# capelet_nrf52.net
KiCad netlist of a schematic drawn in EAGLE
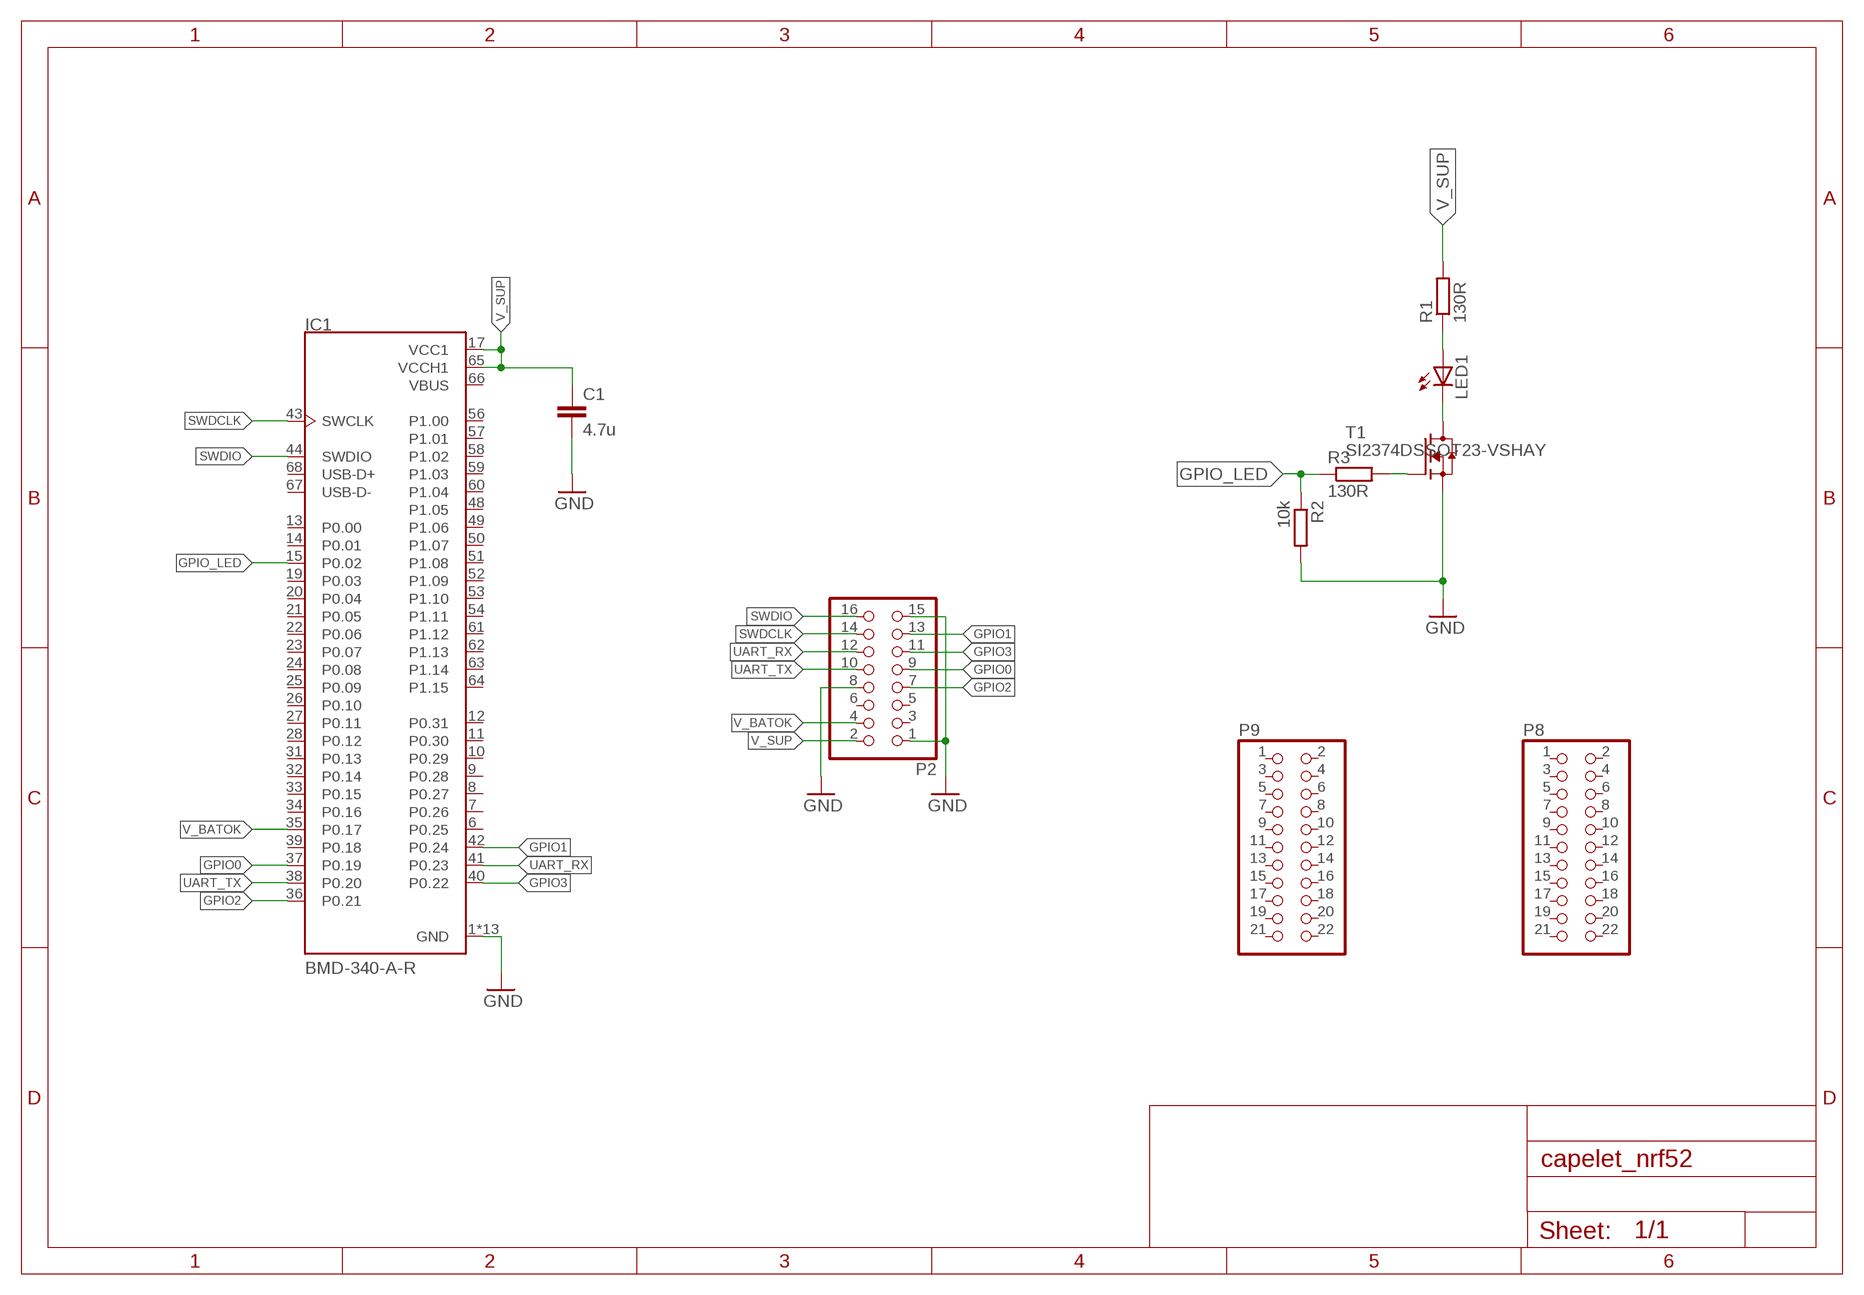
[diagram p0: schematic, sheet 1]

(export (version "E")
  (design (tool "Eeschema 10.0.6"))
  (components
    (comp (ref "C1")
      (value "4.7u")
      (footprint "eagle-import:CAPC1608X95")
      (libsource (lib "eagle-import") (part "C_SMD0603"))
    )
    (comp (ref "IC1")
      (value "BMD-340-A-R")
      (footprint "eagle-import:RIGADO_BMD-340-A-R")
      (fields (field (name "MF") "Rigado"))
      (libsource (lib "eagle-import") (part "BMD-340-A-R"))
    )
    (comp (ref "LED1")
      (value "598-8130-107FLED_0805")
      (footprint "eagle-import:LEDC2012X75")
      (libsource (lib "eagle-import") (part "598-8130-107FLED_0805"))
    )
    (comp (ref "P2")
      (value "PINHD-2X8")
      (footprint "eagle-import:2X08")
      (libsource (lib "eagle-import") (part "PINHD-2X8"))
    )
    (comp (ref "P8")
      (value "PINHD-2X11")
      (footprint "eagle-import:2X11")
      (libsource (lib "eagle-import") (part "PINHD-2X11"))
    )
    (comp (ref "P9")
      (value "PINHD-2X11")
      (footprint "eagle-import:2X11")
      (libsource (lib "eagle-import") (part "PINHD-2X11"))
    )
    (comp (ref "R1")
      (value "130R")
      (footprint "eagle-import:RESC2012X65")
      (libsource (lib "eagle-import") (part "R_SMD0805"))
    )
    (comp (ref "R2")
      (value "10k")
      (footprint "eagle-import:RESC2012X65")
      (libsource (lib "eagle-import") (part "R_SMD0805"))
    )
    (comp (ref "R3")
      (value "130R")
      (footprint "eagle-import:RESC2012X65")
      (libsource (lib "eagle-import") (part "R_SMD0805"))
    )
    (comp (ref "T1")
      (value "SI2374DSSOT23-VSHAY")
      (footprint "eagle-import:SOT95P237X112-3")
      (libsource (lib "eagle-import") (part "SI2374DSSOT23-VSHAY"))
    )
  )
  (nets
    (net (code "1") (name "/VBUS") (class "Default")
      (node (ref "IC1") (pin "66") (pinfunction "VBUS_66") (pintype "power_in"))
    )
    (net (code "2") (name "GND") (class "Default")
      (node (ref "C1") (pin "2") (pinfunction "2_2") (pintype "passive"))
      (node (ref "IC1") (pin "1") (pinfunction "GND_1") (pintype "power_in"))
      (node (ref "IC1") (pin "16") (pinfunction "GND_16") (pintype "power_in"))
      (node (ref "IC1") (pin "18") (pinfunction "GND_18") (pintype "power_in"))
      (node (ref "IC1") (pin "2") (pinfunction "GND_2") (pintype "power_in"))
      (node (ref "IC1") (pin "29") (pinfunction "GND_29") (pintype "power_in"))
      (node (ref "IC1") (pin "3") (pinfunction "GND_3") (pintype "power_in"))
      (node (ref "IC1") (pin "30") (pinfunction "GND_30") (pintype "power_in"))
      (node (ref "IC1") (pin "4") (pinfunction "GND_4") (pintype "power_in"))
      (node (ref "IC1") (pin "45") (pinfunction "GND_45") (pintype "power_in"))
      (node (ref "IC1") (pin "46") (pinfunction "GND_46") (pintype "power_in"))
      (node (ref "IC1") (pin "47") (pinfunction "GND_47") (pintype "power_in"))
      (node (ref "IC1") (pin "5") (pinfunction "GND_5") (pintype "power_in"))
      (node (ref "IC1") (pin "55") (pinfunction "GND_55") (pintype "power_in"))
      (node (ref "P2") (pin "1") (pinfunction "1_1") (pintype "passive"))
      (node (ref "P2") (pin "15") (pinfunction "15_15") (pintype "passive"))
      (node (ref "P2") (pin "8") (pinfunction "8_8") (pintype "passive"))
      (node (ref "R2") (pin "2") (pinfunction "2_2") (pintype "passive"))
      (node (ref "T1") (pin "2") (pinfunction "S_2") (pintype "passive"))
    )
    (net (code "3") (name "GPIO0") (class "Default")
      (node (ref "IC1") (pin "37") (pinfunction "P0.19_37") (pintype "bidirectional"))
      (node (ref "P2") (pin "9") (pinfunction "9_9") (pintype "passive"))
    )
    (net (code "4") (name "GPIO1") (class "Default")
      (node (ref "IC1") (pin "42") (pinfunction "P0.24_42") (pintype "bidirectional"))
      (node (ref "P2") (pin "13") (pinfunction "13_13") (pintype "passive"))
    )
    (net (code "5") (name "GPIO2") (class "Default")
      (node (ref "IC1") (pin "36") (pinfunction "P0.21_36") (pintype "bidirectional"))
      (node (ref "P2") (pin "7") (pinfunction "7_7") (pintype "passive"))
    )
    (net (code "6") (name "GPIO3") (class "Default")
      (node (ref "IC1") (pin "40") (pinfunction "P0.22_40") (pintype "bidirectional"))
      (node (ref "P2") (pin "11") (pinfunction "11_11") (pintype "passive"))
    )
    (net (code "7") (name "GPIO_LED") (class "Default")
      (node (ref "IC1") (pin "15") (pinfunction "P0.02_15") (pintype "bidirectional"))
      (node (ref "R2") (pin "1") (pinfunction "1_1") (pintype "passive"))
      (node (ref "R3") (pin "1") (pinfunction "1_1") (pintype "passive"))
    )
    (net (code "8") (name "Net-(LED1-A)") (class "Default")
      (node (ref "LED1") (pin "2") (pinfunction "A_2") (pintype "passive"))
      (node (ref "R1") (pin "1") (pinfunction "1_1") (pintype "passive"))
    )
    (net (code "9") (name "Net-(LED1-C)") (class "Default")
      (node (ref "LED1") (pin "1") (pinfunction "C_1") (pintype "passive"))
      (node (ref "T1") (pin "3") (pinfunction "D_3") (pintype "passive"))
    )
    (net (code "10") (name "Net-(T1-G)") (class "Default")
      (node (ref "R3") (pin "2") (pinfunction "2_2") (pintype "passive"))
      (node (ref "T1") (pin "1") (pinfunction "G_1") (pintype "passive"))
    )
    (net (code "11") (name "SWDCLK") (class "Default")
      (node (ref "IC1") (pin "43") (pinfunction "SWCLK_43") (pintype "input"))
      (node (ref "P2") (pin "14") (pinfunction "14_14") (pintype "passive"))
    )
    (net (code "12") (name "SWDIO") (class "Default")
      (node (ref "IC1") (pin "44") (pinfunction "SWDIO_44") (pintype "bidirectional"))
      (node (ref "P2") (pin "16") (pinfunction "16_16") (pintype "passive"))
    )
    (net (code "13") (name "UART_RX") (class "Default")
      (node (ref "IC1") (pin "41") (pinfunction "P0.23_41") (pintype "bidirectional"))
      (node (ref "P2") (pin "12") (pinfunction "12_12") (pintype "passive"))
    )
    (net (code "14") (name "UART_TX") (class "Default")
      (node (ref "IC1") (pin "38") (pinfunction "P0.20_38") (pintype "bidirectional"))
      (node (ref "P2") (pin "10") (pinfunction "10_10") (pintype "passive"))
    )
    (net (code "15") (name "V_BATOK") (class "Default")
      (node (ref "IC1") (pin "35") (pinfunction "P0.17_35") (pintype "bidirectional"))
      (node (ref "P2") (pin "4") (pinfunction "4_4") (pintype "passive"))
    )
    (net (code "16") (name "V_SUP") (class "Default")
      (node (ref "C1") (pin "1") (pinfunction "1_1") (pintype "passive"))
      (node (ref "IC1") (pin "17") (pinfunction "VCC1_17") (pintype "power_in"))
      (node (ref "IC1") (pin "65") (pinfunction "VCCH1_65") (pintype "power_in"))
      (node (ref "P2") (pin "2") (pinfunction "2_2") (pintype "passive"))
      (node (ref "R1") (pin "2") (pinfunction "2_2") (pintype "passive"))
    )
    (net (code "17") (name "unconnected-(IC1-P0.00-Pad13)") (class "Default")
      (node (ref "IC1") (pin "13") (pinfunction "P0.00_13") (pintype "bidirectional"))
    )
    (net (code "18") (name "unconnected-(IC1-P0.01-Pad14)") (class "Default")
      (node (ref "IC1") (pin "14") (pinfunction "P0.01_14") (pintype "bidirectional"))
    )
    (net (code "19") (name "unconnected-(IC1-P0.03-Pad19)") (class "Default")
      (node (ref "IC1") (pin "19") (pinfunction "P0.03_19") (pintype "bidirectional"))
    )
    (net (code "20") (name "unconnected-(IC1-P0.04-Pad20)") (class "Default")
      (node (ref "IC1") (pin "20") (pinfunction "P0.04_20") (pintype "bidirectional"))
    )
    (net (code "21") (name "unconnected-(IC1-P0.05-Pad21)") (class "Default")
      (node (ref "IC1") (pin "21") (pinfunction "P0.05_21") (pintype "bidirectional"))
    )
    (net (code "22") (name "unconnected-(IC1-P0.06-Pad22)") (class "Default")
      (node (ref "IC1") (pin "22") (pinfunction "P0.06_22") (pintype "bidirectional"))
    )
    (net (code "23") (name "unconnected-(IC1-P0.07-Pad23)") (class "Default")
      (node (ref "IC1") (pin "23") (pinfunction "P0.07_23") (pintype "bidirectional"))
    )
    (net (code "24") (name "unconnected-(IC1-P0.08-Pad24)") (class "Default")
      (node (ref "IC1") (pin "24") (pinfunction "P0.08_24") (pintype "bidirectional"))
    )
    (net (code "25") (name "unconnected-(IC1-P0.09-Pad25)") (class "Default")
      (node (ref "IC1") (pin "25") (pinfunction "P0.09_25") (pintype "bidirectional"))
    )
    (net (code "26") (name "unconnected-(IC1-P0.10-Pad26)") (class "Default")
      (node (ref "IC1") (pin "26") (pinfunction "P0.10_26") (pintype "bidirectional"))
    )
    (net (code "27") (name "unconnected-(IC1-P0.11-Pad27)") (class "Default")
      (node (ref "IC1") (pin "27") (pinfunction "P0.11_27") (pintype "bidirectional"))
    )
    (net (code "28") (name "unconnected-(IC1-P0.12-Pad28)") (class "Default")
      (node (ref "IC1") (pin "28") (pinfunction "P0.12_28") (pintype "bidirectional"))
    )
    (net (code "29") (name "unconnected-(IC1-P0.13-Pad31)") (class "Default")
      (node (ref "IC1") (pin "31") (pinfunction "P0.13_31") (pintype "bidirectional"))
    )
    (net (code "30") (name "unconnected-(IC1-P0.14-Pad32)") (class "Default")
      (node (ref "IC1") (pin "32") (pinfunction "P0.14_32") (pintype "bidirectional"))
    )
    (net (code "31") (name "unconnected-(IC1-P0.15-Pad33)") (class "Default")
      (node (ref "IC1") (pin "33") (pinfunction "P0.15_33") (pintype "bidirectional"))
    )
    (net (code "32") (name "unconnected-(IC1-P0.16-Pad34)") (class "Default")
      (node (ref "IC1") (pin "34") (pinfunction "P0.16_34") (pintype "bidirectional"))
    )
    (net (code "33") (name "unconnected-(IC1-P0.18-Pad39)") (class "Default")
      (node (ref "IC1") (pin "39") (pinfunction "P0.18_39") (pintype "bidirectional"))
    )
    (net (code "34") (name "unconnected-(IC1-P0.25-Pad6)") (class "Default")
      (node (ref "IC1") (pin "6") (pinfunction "P0.25_6") (pintype "bidirectional"))
    )
    (net (code "35") (name "unconnected-(IC1-P0.26-Pad7)") (class "Default")
      (node (ref "IC1") (pin "7") (pinfunction "P0.26_7") (pintype "bidirectional"))
    )
    (net (code "36") (name "unconnected-(IC1-P0.27-Pad8)") (class "Default")
      (node (ref "IC1") (pin "8") (pinfunction "P0.27_8") (pintype "bidirectional"))
    )
    (net (code "37") (name "unconnected-(IC1-P0.28-Pad9)") (class "Default")
      (node (ref "IC1") (pin "9") (pinfunction "P0.28_9") (pintype "bidirectional"))
    )
    (net (code "38") (name "unconnected-(IC1-P0.29-Pad10)") (class "Default")
      (node (ref "IC1") (pin "10") (pinfunction "P0.29_10") (pintype "bidirectional"))
    )
    (net (code "39") (name "unconnected-(IC1-P0.30-Pad11)") (class "Default")
      (node (ref "IC1") (pin "11") (pinfunction "P0.30_11") (pintype "bidirectional"))
    )
    (net (code "40") (name "unconnected-(IC1-P0.31-Pad12)") (class "Default")
      (node (ref "IC1") (pin "12") (pinfunction "P0.31_12") (pintype "bidirectional"))
    )
    (net (code "41") (name "unconnected-(IC1-P1.00-Pad56)") (class "Default")
      (node (ref "IC1") (pin "56") (pinfunction "P1.00_56") (pintype "bidirectional"))
    )
    (net (code "42") (name "unconnected-(IC1-P1.01-Pad57)") (class "Default")
      (node (ref "IC1") (pin "57") (pinfunction "P1.01_57") (pintype "bidirectional"))
    )
    (net (code "43") (name "unconnected-(IC1-P1.02-Pad58)") (class "Default")
      (node (ref "IC1") (pin "58") (pinfunction "P1.02_58") (pintype "bidirectional"))
    )
    (net (code "44") (name "unconnected-(IC1-P1.03-Pad59)") (class "Default")
      (node (ref "IC1") (pin "59") (pinfunction "P1.03_59") (pintype "bidirectional"))
    )
    (net (code "45") (name "unconnected-(IC1-P1.04-Pad60)") (class "Default")
      (node (ref "IC1") (pin "60") (pinfunction "P1.04_60") (pintype "bidirectional"))
    )
    (net (code "46") (name "unconnected-(IC1-P1.05-Pad48)") (class "Default")
      (node (ref "IC1") (pin "48") (pinfunction "P1.05_48") (pintype "bidirectional"))
    )
    (net (code "47") (name "unconnected-(IC1-P1.06-Pad49)") (class "Default")
      (node (ref "IC1") (pin "49") (pinfunction "P1.06_49") (pintype "bidirectional"))
    )
    (net (code "48") (name "unconnected-(IC1-P1.07-Pad50)") (class "Default")
      (node (ref "IC1") (pin "50") (pinfunction "P1.07_50") (pintype "bidirectional"))
    )
    (net (code "49") (name "unconnected-(IC1-P1.08-Pad51)") (class "Default")
      (node (ref "IC1") (pin "51") (pinfunction "P1.08_51") (pintype "bidirectional"))
    )
    (net (code "50") (name "unconnected-(IC1-P1.09-Pad52)") (class "Default")
      (node (ref "IC1") (pin "52") (pinfunction "P1.09_52") (pintype "bidirectional"))
    )
    (net (code "51") (name "unconnected-(IC1-P1.10-Pad53)") (class "Default")
      (node (ref "IC1") (pin "53") (pinfunction "P1.10_53") (pintype "bidirectional"))
    )
    (net (code "52") (name "unconnected-(IC1-P1.11-Pad54)") (class "Default")
      (node (ref "IC1") (pin "54") (pinfunction "P1.11_54") (pintype "bidirectional"))
    )
    (net (code "53") (name "unconnected-(IC1-P1.12-Pad61)") (class "Default")
      (node (ref "IC1") (pin "61") (pinfunction "P1.12_61") (pintype "bidirectional"))
    )
    (net (code "54") (name "unconnected-(IC1-P1.13-Pad62)") (class "Default")
      (node (ref "IC1") (pin "62") (pinfunction "P1.13_62") (pintype "bidirectional"))
    )
    (net (code "55") (name "unconnected-(IC1-P1.14-Pad63)") (class "Default")
      (node (ref "IC1") (pin "63") (pinfunction "P1.14_63") (pintype "bidirectional"))
    )
    (net (code "56") (name "unconnected-(IC1-P1.15-Pad64)") (class "Default")
      (node (ref "IC1") (pin "64") (pinfunction "P1.15_64") (pintype "bidirectional"))
    )
    (net (code "57") (name "unconnected-(IC1-USB-D+-Pad68)") (class "Default")
      (node (ref "IC1") (pin "68") (pinfunction "USB-D+_68") (pintype "bidirectional"))
    )
    (net (code "58") (name "unconnected-(IC1-USB-D--Pad67)") (class "Default")
      (node (ref "IC1") (pin "67") (pinfunction "USB-D-_67") (pintype "bidirectional"))
    )
    (net (code "59") (name "unconnected-(P2-Pad3)") (class "Default")
      (node (ref "P2") (pin "3") (pinfunction "3_3") (pintype "passive"))
    )
    (net (code "60") (name "unconnected-(P2-Pad5)") (class "Default")
      (node (ref "P2") (pin "5") (pinfunction "5_5") (pintype "passive"))
    )
    (net (code "61") (name "unconnected-(P2-Pad6)") (class "Default")
      (node (ref "P2") (pin "6") (pinfunction "6_6") (pintype "passive"))
    )
    (net (code "62") (name "unconnected-(P8-Pad1)") (class "Default")
      (node (ref "P8") (pin "1") (pinfunction "1_1") (pintype "passive"))
    )
    (net (code "63") (name "unconnected-(P8-Pad2)") (class "Default")
      (node (ref "P8") (pin "2") (pinfunction "2_2") (pintype "passive"))
    )
    (net (code "64") (name "unconnected-(P8-Pad3)") (class "Default")
      (node (ref "P8") (pin "3") (pinfunction "3_3") (pintype "passive"))
    )
    (net (code "65") (name "unconnected-(P8-Pad4)") (class "Default")
      (node (ref "P8") (pin "4") (pinfunction "4_4") (pintype "passive"))
    )
    (net (code "66") (name "unconnected-(P8-Pad5)") (class "Default")
      (node (ref "P8") (pin "5") (pinfunction "5_5") (pintype "passive"))
    )
    (net (code "67") (name "unconnected-(P8-Pad6)") (class "Default")
      (node (ref "P8") (pin "6") (pinfunction "6_6") (pintype "passive"))
    )
    (net (code "68") (name "unconnected-(P8-Pad7)") (class "Default")
      (node (ref "P8") (pin "7") (pinfunction "7_7") (pintype "passive"))
    )
    (net (code "69") (name "unconnected-(P8-Pad8)") (class "Default")
      (node (ref "P8") (pin "8") (pinfunction "8_8") (pintype "passive"))
    )
    (net (code "70") (name "unconnected-(P8-Pad9)") (class "Default")
      (node (ref "P8") (pin "9") (pinfunction "9_9") (pintype "passive"))
    )
    (net (code "71") (name "unconnected-(P8-Pad10)") (class "Default")
      (node (ref "P8") (pin "10") (pinfunction "10_10") (pintype "passive"))
    )
    (net (code "72") (name "unconnected-(P8-Pad11)") (class "Default")
      (node (ref "P8") (pin "11") (pinfunction "11_11") (pintype "passive"))
    )
    (net (code "73") (name "unconnected-(P8-Pad12)") (class "Default")
      (node (ref "P8") (pin "12") (pinfunction "12_12") (pintype "passive"))
    )
    (net (code "74") (name "unconnected-(P8-Pad13)") (class "Default")
      (node (ref "P8") (pin "13") (pinfunction "13_13") (pintype "passive"))
    )
    (net (code "75") (name "unconnected-(P8-Pad14)") (class "Default")
      (node (ref "P8") (pin "14") (pinfunction "14_14") (pintype "passive"))
    )
    (net (code "76") (name "unconnected-(P8-Pad15)") (class "Default")
      (node (ref "P8") (pin "15") (pinfunction "15_15") (pintype "passive"))
    )
    (net (code "77") (name "unconnected-(P8-Pad16)") (class "Default")
      (node (ref "P8") (pin "16") (pinfunction "16_16") (pintype "passive"))
    )
    (net (code "78") (name "unconnected-(P8-Pad17)") (class "Default")
      (node (ref "P8") (pin "17") (pinfunction "17_17") (pintype "passive"))
    )
    (net (code "79") (name "unconnected-(P8-Pad18)") (class "Default")
      (node (ref "P8") (pin "18") (pinfunction "18_18") (pintype "passive"))
    )
    (net (code "80") (name "unconnected-(P8-Pad19)") (class "Default")
      (node (ref "P8") (pin "19") (pinfunction "19_19") (pintype "passive"))
    )
    (net (code "81") (name "unconnected-(P8-Pad20)") (class "Default")
      (node (ref "P8") (pin "20") (pinfunction "20_20") (pintype "passive"))
    )
    (net (code "82") (name "unconnected-(P8-Pad21)") (class "Default")
      (node (ref "P8") (pin "21") (pinfunction "21_21") (pintype "passive"))
    )
    (net (code "83") (name "unconnected-(P8-Pad22)") (class "Default")
      (node (ref "P8") (pin "22") (pinfunction "22_22") (pintype "passive"))
    )
    (net (code "84") (name "unconnected-(P9-Pad1)") (class "Default")
      (node (ref "P9") (pin "1") (pinfunction "1_1") (pintype "passive"))
    )
    (net (code "85") (name "unconnected-(P9-Pad2)") (class "Default")
      (node (ref "P9") (pin "2") (pinfunction "2_2") (pintype "passive"))
    )
    (net (code "86") (name "unconnected-(P9-Pad3)") (class "Default")
      (node (ref "P9") (pin "3") (pinfunction "3_3") (pintype "passive"))
    )
    (net (code "87") (name "unconnected-(P9-Pad4)") (class "Default")
      (node (ref "P9") (pin "4") (pinfunction "4_4") (pintype "passive"))
    )
    (net (code "88") (name "unconnected-(P9-Pad5)") (class "Default")
      (node (ref "P9") (pin "5") (pinfunction "5_5") (pintype "passive"))
    )
    (net (code "89") (name "unconnected-(P9-Pad6)") (class "Default")
      (node (ref "P9") (pin "6") (pinfunction "6_6") (pintype "passive"))
    )
    (net (code "90") (name "unconnected-(P9-Pad7)") (class "Default")
      (node (ref "P9") (pin "7") (pinfunction "7_7") (pintype "passive"))
    )
    (net (code "91") (name "unconnected-(P9-Pad8)") (class "Default")
      (node (ref "P9") (pin "8") (pinfunction "8_8") (pintype "passive"))
    )
    (net (code "92") (name "unconnected-(P9-Pad9)") (class "Default")
      (node (ref "P9") (pin "9") (pinfunction "9_9") (pintype "passive"))
    )
    (net (code "93") (name "unconnected-(P9-Pad10)") (class "Default")
      (node (ref "P9") (pin "10") (pinfunction "10_10") (pintype "passive"))
    )
    (net (code "94") (name "unconnected-(P9-Pad11)") (class "Default")
      (node (ref "P9") (pin "11") (pinfunction "11_11") (pintype "passive"))
    )
    (net (code "95") (name "unconnected-(P9-Pad12)") (class "Default")
      (node (ref "P9") (pin "12") (pinfunction "12_12") (pintype "passive"))
    )
    (net (code "96") (name "unconnected-(P9-Pad13)") (class "Default")
      (node (ref "P9") (pin "13") (pinfunction "13_13") (pintype "passive"))
    )
    (net (code "97") (name "unconnected-(P9-Pad14)") (class "Default")
      (node (ref "P9") (pin "14") (pinfunction "14_14") (pintype "passive"))
    )
    (net (code "98") (name "unconnected-(P9-Pad15)") (class "Default")
      (node (ref "P9") (pin "15") (pinfunction "15_15") (pintype "passive"))
    )
    (net (code "99") (name "unconnected-(P9-Pad16)") (class "Default")
      (node (ref "P9") (pin "16") (pinfunction "16_16") (pintype "passive"))
    )
    (net (code "100") (name "unconnected-(P9-Pad17)") (class "Default")
      (node (ref "P9") (pin "17") (pinfunction "17_17") (pintype "passive"))
    )
    (net (code "101") (name "unconnected-(P9-Pad18)") (class "Default")
      (node (ref "P9") (pin "18") (pinfunction "18_18") (pintype "passive"))
    )
    (net (code "102") (name "unconnected-(P9-Pad19)") (class "Default")
      (node (ref "P9") (pin "19") (pinfunction "19_19") (pintype "passive"))
    )
    (net (code "103") (name "unconnected-(P9-Pad20)") (class "Default")
      (node (ref "P9") (pin "20") (pinfunction "20_20") (pintype "passive"))
    )
    (net (code "104") (name "unconnected-(P9-Pad21)") (class "Default")
      (node (ref "P9") (pin "21") (pinfunction "21_21") (pintype "passive"))
    )
    (net (code "105") (name "unconnected-(P9-Pad22)") (class "Default")
      (node (ref "P9") (pin "22") (pinfunction "22_22") (pintype "passive"))
    )
  )
)
